# Deck.net
KiCad netlist of a schematic drawn in Altium Designer
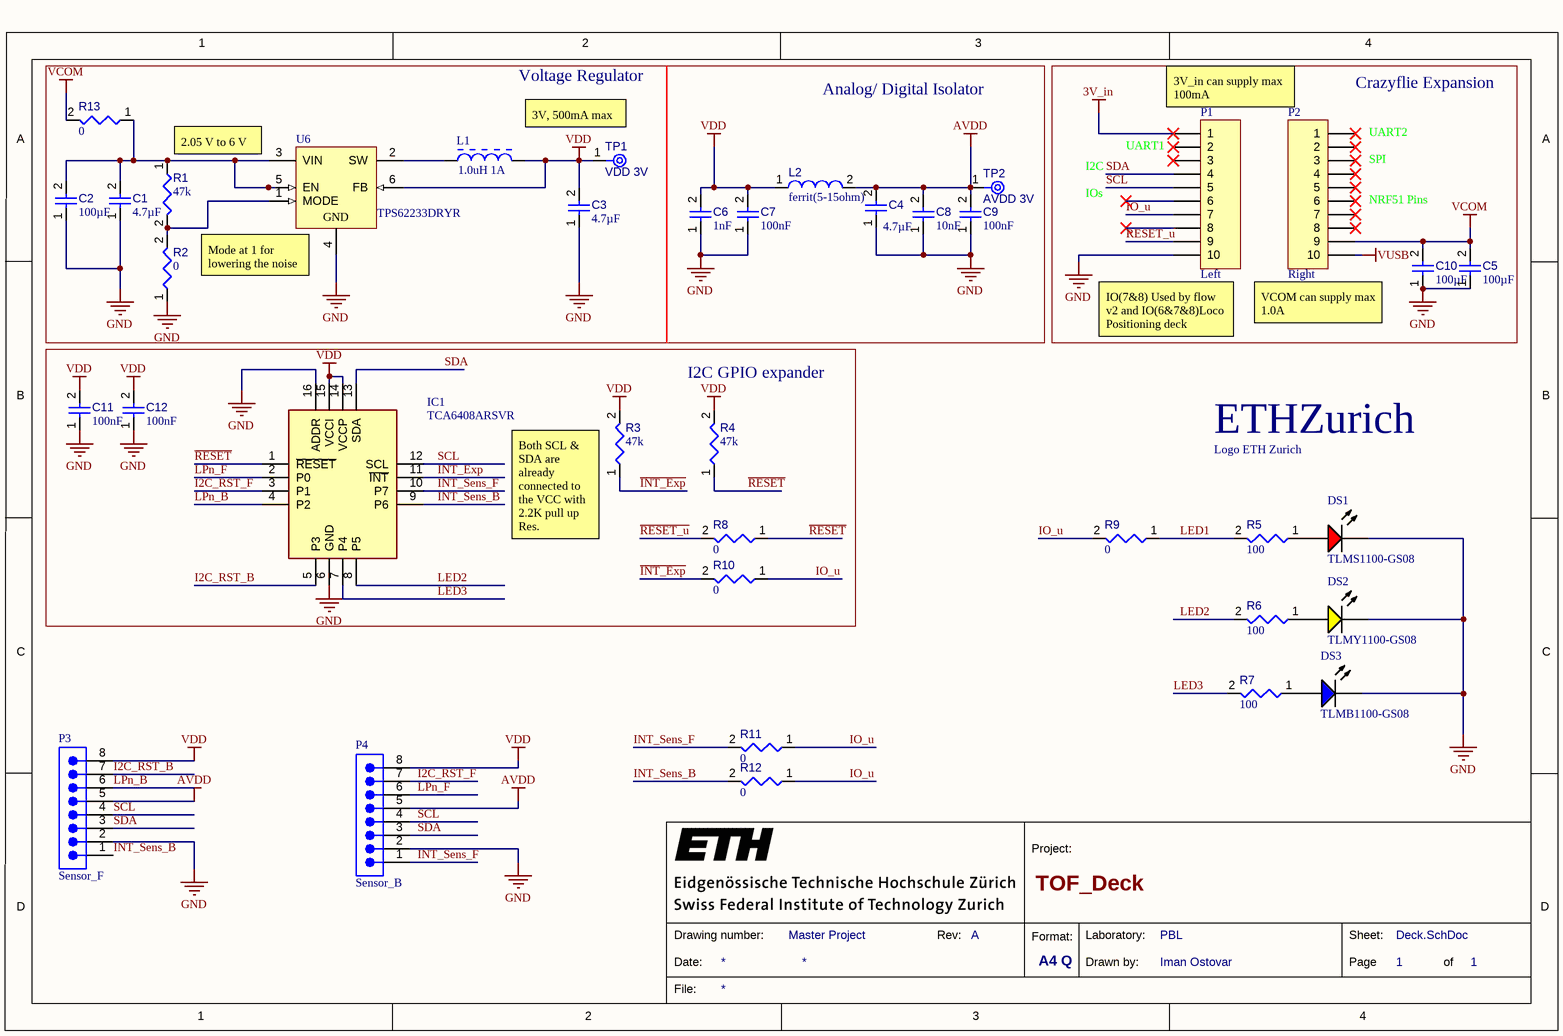
[diagram p0: Deck.SchDoc]

(export (version "E")
  (design (tool "Eeschema 10.0.6"))
  (components
    (comp (ref "A1")
      (value "Logo ETH Zurich")
      (footprint "eth-zurich_3mm")
      (libsource (lib "Sensor_Node_Shield") (part "CMP-00038-1"))
    )
    (comp (ref "C1")
      (value "4.7µF")
      (footprint "CAPC1005X55X25ML5T10")
      (description "Chip Capacitor, 1 uF, +/- 10%, 6.3 V, 1005 (0402 Metric)")
      (fields (field (name "TOLERANCE") "10%") (field (name "Comment") "Capacitor 1 uF +/- 10% 6.3 V 1005"))
      (libsource (lib "ETH Zurich") (part "CAP-NP-2"))
    )
    (comp (ref "C2")
      (value "100µF")
      (footprint "CAPC0805(2012)145_L")
      (description "Chip Capacitor, 100µF +/-20%, 6.3V, 0805, Thickness 1.45 mm")
      (fields (field (name "TOLERANCE") "10%") (field (name "Comment") "Capacitor 100µF +/-20% 6.3V 0805"))
      (libsource (lib "ETH Zurich") (part "CAP-NP-2"))
    )
    (comp (ref "C3")
      (value "4.7µF")
      (footprint "CAPC1005X55X25ML5T10")
      (description "Chip Capacitor, 1 uF, +/- 10%, 6.3 V, 1005 (0402 Metric)")
      (fields (field (name "TOLERANCE") "10%") (field (name "Comment") "Capacitor 1 uF +/- 10% 6.3 V 1005"))
      (libsource (lib "ETH Zurich") (part "CAP-NP-2"))
    )
    (comp (ref "C4")
      (value "4.7µF")
      (footprint "CAPC1005X55X25ML5T10")
      (description "Chip Capacitor, 1 uF, +/- 10%, 6.3 V, 1005 (0402 Metric)")
      (fields (field (name "TOLERANCE") "10%") (field (name "Comment") "Capacitor 1 uF +/- 10% 6.3 V 1005"))
      (libsource (lib "ETH Zurich") (part "CAP-NP-2"))
    )
    (comp (ref "C5")
      (value "100µF")
      (footprint "CAPC0805(2012)145_L")
      (description "Chip Capacitor, 100µF +/-20%, 6.3V, 0805, Thickness 1.45 mm")
      (fields (field (name "TOLERANCE") "10%") (field (name "Comment") "Capacitor 100µF +/-20% 6.3V 0805"))
      (libsource (lib "ETH Zurich") (part "CAP-NP-2"))
    )
    (comp (ref "C6")
      (value "1nF")
      (footprint "CAPC0402(1005)60_L")
      (description "Chip Capacitor, 100nF +/-20%, 25V, 0402, Thickness 0.6 mm")
      (fields (field (name "TOLERANCE") "10%") (field (name "Comment") "Capacitor 100nF +/-20% 25V 0402"))
      (libsource (lib "ETH Zurich") (part "CAP-NP-2"))
    )
    (comp (ref "C7")
      (value "100nF")
      (footprint "CAPC0402(1005)60_L")
      (description "Chip Capacitor, 100nF +/-20%, 25V, 0402, Thickness 0.6 mm")
      (fields (field (name "TOLERANCE") "10%") (field (name "Comment") "Capacitor 100nF +/-20% 25V 0402"))
      (libsource (lib "ETH Zurich") (part "CAP-NP-2"))
    )
    (comp (ref "C8")
      (value "10nF")
      (footprint "CAPC0402(1005)60_L")
      (description "Chip Capacitor, 100nF +/-20%, 25V, 0402, Thickness 0.6 mm")
      (fields (field (name "TOLERANCE") "10%") (field (name "Comment") "Capacitor 100nF +/-20% 25V 0402"))
      (libsource (lib "ETH Zurich") (part "CAP-NP-2"))
    )
    (comp (ref "C9")
      (value "100nF")
      (footprint "CAPC0402(1005)60_L")
      (description "Chip Capacitor, 100nF +/-20%, 25V, 0402, Thickness 0.6 mm")
      (fields (field (name "TOLERANCE") "10%") (field (name "Comment") "Capacitor 100nF +/-20% 25V 0402"))
      (libsource (lib "ETH Zurich") (part "CAP-NP-2"))
    )
    (comp (ref "C10")
      (value "100µF")
      (footprint "CAPC0805(2012)145_L")
      (description "Chip Capacitor, 100µF +/-20%, 6.3V, 0805, Thickness 1.45 mm")
      (fields (field (name "TOLERANCE") "10%") (field (name "Comment") "Capacitor 100µF +/-20% 6.3V 0805"))
      (libsource (lib "ETH Zurich") (part "CAP-NP-2"))
    )
    (comp (ref "C11")
      (value "100nF")
      (footprint "CAPC0402(1005)60_L")
      (description "Chip Capacitor, 100nF +/-20%, 25V, 0402, Thickness 0.6 mm")
      (fields (field (name "TOLERANCE") "10%") (field (name "Comment") "Capacitor 100nF +/-20% 25V 0402"))
      (libsource (lib "ETH Zurich") (part "CAP-NP-2"))
    )
    (comp (ref "C12")
      (value "100nF")
      (footprint "CAPC0402(1005)60_L")
      (description "Chip Capacitor, 100nF +/-20%, 25V, 0402, Thickness 0.6 mm")
      (fields (field (name "TOLERANCE") "10%") (field (name "Comment") "Capacitor 100nF +/-20% 25V 0402"))
      (libsource (lib "ETH Zurich") (part "CAP-NP-2"))
    )
    (comp (ref "DS1")
      (value "TLMS1100-GS08")
      (footprint "VISH-TLMX1100_V")
      (description "Red Led, 20mA, 2.1 V, -40 to 100 degC, 2-Pin SMD (0603), RoHS, Tape and Reel")
      (fields (field (name "MANUFACTURER") "Vishay Semiconductor") (field (name "POWER") "90mW"))
      (libsource (lib "ETH Zurich") (part "LED-RED-AK-2"))
    )
    (comp (ref "DS2")
      (value "TLMY1100-GS08")
      (footprint "VISH-TLMX1100-2_V")
      (description "Yellow LED, 20 mA, 2.1 V, -40 to 100 degC, 2-Pin SMD (0603), RoHS, Tape and Reel")
      (fields (field (name "MANUFACTURER") "Vishay Semiconductor") (field (name "POWER") "90mW"))
      (libsource (lib "ETH Zurich") (part "LED-YELLOW-AK-2"))
    )
    (comp (ref "DS3")
      (value "TLMB1100-GS08")
      (footprint "VISH-TLMX1100-2_V")
      (description "Blue LED, 10 mA, 3.9 V, -40 to 100 degC, 2-Pin SMD (0603), RoHS, Tape and Reel")
      (fields (field (name "POWER") "68mW") (field (name "MANUFACTURER") "Vishay Semiconductor"))
      (libsource (lib "ETH Zurich") (part "LED-BLUE-AK-2"))
    )
    (comp (ref "IC1")
      (value "TCA6408ARSVR")
      (footprint "SamacSys:QFN40P180X260X55-16N")
      (description "Integrated Circuit")
      (fields (field (name "MOUSER PART NUMBER") "595-TCA6408ARSVR"))
      (libsource (lib "*") (part "TCA6408ARSVR"))
    )
    (comp (ref "L1")
      (value "1.0uH 1A")
      (footprint "INDC2013X105X50ML20T20")
      (description "1.0uH 1150mA")
      (fields (field (name "TOLERANCE") "25%") (field (name "MANUFACTURER") "Murata"))
      (libsource (lib "ETH Zurich") (part "IND-FB-2"))
    )
    (comp (ref "L2")
      (value "ferrit(5-15ohm)")
      (footprint "MURA-LQP15MN3N6B02D-2_M")
      (description "Inductor, 500 MHz, 500 mA, 5 Ohm, -40 to 85 degC, 01005 (0402 Metric),")
      (fields (field (name "MANUFACTURER") "Murata") (field (name "Comment") "LQP15MN3N6B02D"))
      (libsource (lib "ETH Zurich") (part "IND-2"))
    )
    (comp (ref "P1")
      (value "Left")
      (footprint "crazyflie-header:PCBComponent_1")
      (description "Header, 10-Pin")
      (fields (field (name "PUBLISHER") "Altium Limited"))
      (libsource (lib "") (part "MHDR1X10_1"))
    )
    (comp (ref "P2")
      (value "Right")
      (footprint "crazyflie-header:PCBComponent_1")
      (description "Header, 10-Pin")
      (fields (field (name "PUBLISHER") "Altium Limited"))
      (libsource (lib "Miscellaneous Connectors") (part "MHDR1X10"))
    )
    (comp (ref "P3")
      (value "Sensor_F")
      (footprint "M50-3930842")
      (description "Connector Header Through Hole, Right Angle 8 position 0.050\" (1.27mm)")
      (libsource (lib "ETHZ Vault") (part "CON-1x8-Male"))
    )
    (comp (ref "P4")
      (value "Sensor_B")
      (footprint "M50-3930842")
      (description "Connector Header Through Hole, Right Angle 8 position 0.050\" (1.27mm)")
      (libsource (lib "ETHZ Vault") (part "CON-1x8-Male"))
    )
    (comp (ref "R1")
      (value "47k")
      (footprint "RESC0402(1005)_L")
      (description "Chip Resistor, 47,5 kOhms, +/-1 %, 63 mW, -55 to 155 degC, 0402")
      (fields (field (name "POWER") "63mW") (field (name "TOLERANCE") "1%"))
      (libsource (lib "ETH Zurich") (part "RES-2"))
    )
    (comp (ref "R2")
      (value "0")
      (footprint "RESC0402(1005)_L")
      (description "Jumper 0402")
      (libsource (lib "ETH Zurich") (part "RES-2"))
    )
    (comp (ref "R3")
      (value "47k")
      (footprint "RESC0402(1005)_L")
      (description "Chip Resistor, 47,5 kOhms, +/-1 %, 63 mW, -55 to 155 degC, 0402")
      (fields (field (name "POWER") "63mW") (field (name "TOLERANCE") "1%"))
      (libsource (lib "ETH Zurich") (part "RES-2"))
    )
    (comp (ref "R4")
      (value "47k")
      (footprint "RESC0402(1005)_L")
      (description "Chip Resistor, 47,5 kOhms, +/-1 %, 63 mW, -55 to 155 degC, 0402")
      (fields (field (name "POWER") "63mW") (field (name "TOLERANCE") "1%"))
      (libsource (lib "ETH Zurich") (part "RES-2"))
    )
    (comp (ref "R5")
      (value "100")
      (footprint "RESC0402(1005)_L")
      (description "Chip Resistor, 47,5 kOhms, +/-1 %, 63 mW, -55 to 155 degC, 0402")
      (fields (field (name "POWER") "63mW") (field (name "TOLERANCE") "1%"))
      (libsource (lib "ETH Zurich") (part "RES-2"))
    )
    (comp (ref "R6")
      (value "100")
      (footprint "RESC0402(1005)_L")
      (description "Chip Resistor, 47,5 kOhms, +/-1 %, 63 mW, -55 to 155 degC, 0402")
      (fields (field (name "POWER") "63mW") (field (name "TOLERANCE") "1%"))
      (libsource (lib "ETH Zurich") (part "RES-2"))
    )
    (comp (ref "R7")
      (value "100")
      (footprint "RESC0402(1005)_L")
      (description "Chip Resistor, 47,5 kOhms, +/-1 %, 63 mW, -55 to 155 degC, 0402")
      (fields (field (name "POWER") "63mW") (field (name "TOLERANCE") "1%"))
      (libsource (lib "ETH Zurich") (part "RES-2"))
    )
    (comp (ref "R8")
      (value "0")
      (footprint "RESC0402(1005)_L")
      (description "Jumper 0402")
      (libsource (lib "ETH Zurich") (part "RES-2"))
    )
    (comp (ref "R9")
      (value "0")
      (footprint "RESC0402(1005)_L")
      (description "Jumper 0402")
      (libsource (lib "ETH Zurich") (part "RES-2"))
    )
    (comp (ref "R10")
      (value "0")
      (footprint "RESC0402(1005)_L")
      (description "Jumper 0402")
      (libsource (lib "ETH Zurich") (part "RES-2"))
    )
    (comp (ref "R11")
      (value "0")
      (footprint "RESC0402(1005)_L")
      (description "Jumper 0402")
      (libsource (lib "ETH Zurich") (part "RES-2"))
    )
    (comp (ref "R12")
      (value "0")
      (footprint "RESC0402(1005)_L")
      (description "Jumper 0402")
      (libsource (lib "ETH Zurich") (part "RES-2"))
    )
    (comp (ref "R13")
      (value "0")
      (footprint "RESC0402(1005)_L")
      (description "Current sensing jumper OR Fuse")
      (fields (field (name "Comment") "Jumper 0402"))
      (libsource (lib "ETH Zurich") (part "RES-2"))
    )
    (comp (ref "TP1")
      (value "VDD 3V")
      (footprint "TP06R")
      (description "0.6mm round")
      (libsource (lib "ETH Zurich") (part "CMP-001-0001-4"))
    )
    (comp (ref "TP2")
      (value "AVDD 3V")
      (footprint "TP06R")
      (description "0.6mm round")
      (libsource (lib "ETH Zurich") (part "CMP-001-0001-4"))
    )
    (comp (ref "U6")
      (value "TPS62233DRYR")
      (footprint "DRY0006A")
      (fields (field (name "MANUFACTURER") "Texas Instruments"))
      (libsource (lib "Altium Content Vault") (part "TI-TPS62233DRY6"))
    )
  )
  (nets
    (net (code "1") (name "/I2C_RST_B") (class "Default")
      (node (ref "IC1") (pin "5") (pinfunction "P3_5") (pintype "passive"))
      (node (ref "P3") (pin "7") (pinfunction "7_7") (pintype "passive"))
    )
    (net (code "2") (name "/I2C_RST_F") (class "Default")
      (node (ref "IC1") (pin "3") (pinfunction "P1_3") (pintype "passive"))
      (node (ref "P4") (pin "7") (pinfunction "7_7") (pintype "passive"))
    )
    (net (code "3") (name "/INT_Exp") (class "Default")
      (node (ref "IC1") (pin "11") (pinfunction "~{INT}_11") (pintype "passive"))
      (node (ref "R10") (pin "2") (pinfunction "2_2") (pintype "passive"))
      (node (ref "R3") (pin "1") (pinfunction "1_1") (pintype "passive"))
    )
    (net (code "4") (name "/INT_Sens_B") (class "Default")
      (node (ref "IC1") (pin "9") (pinfunction "P6_9") (pintype "passive"))
      (node (ref "P3") (pin "1") (pinfunction "1_1") (pintype "passive"))
      (node (ref "R12") (pin "2") (pinfunction "2_2") (pintype "passive"))
    )
    (net (code "5") (name "/INT_Sens_F") (class "Default")
      (node (ref "IC1") (pin "10") (pinfunction "P7_10") (pintype "passive"))
      (node (ref "P4") (pin "1") (pinfunction "1_1") (pintype "passive"))
      (node (ref "R11") (pin "2") (pinfunction "2_2") (pintype "passive"))
    )
    (net (code "6") (name "/IO_u") (class "Default")
      (node (ref "P1") (pin "7") (pinfunction "7_7") (pintype "passive"))
      (node (ref "R10") (pin "1") (pinfunction "1_1") (pintype "passive"))
      (node (ref "R11") (pin "1") (pinfunction "1_1") (pintype "passive"))
      (node (ref "R12") (pin "1") (pinfunction "1_1") (pintype "passive"))
      (node (ref "R9") (pin "2") (pinfunction "2_2") (pintype "passive"))
    )
    (net (code "7") (name "/LED1") (class "Default")
      (node (ref "R5") (pin "2") (pinfunction "2_2") (pintype "passive"))
      (node (ref "R9") (pin "1") (pinfunction "1_1") (pintype "passive"))
    )
    (net (code "8") (name "/LED2") (class "Default")
      (node (ref "IC1") (pin "8") (pinfunction "P5_8") (pintype "passive"))
      (node (ref "R6") (pin "2") (pinfunction "2_2") (pintype "passive"))
    )
    (net (code "9") (name "/LED3") (class "Default")
      (node (ref "IC1") (pin "7") (pinfunction "P4_7") (pintype "passive"))
      (node (ref "R7") (pin "2") (pinfunction "2_2") (pintype "passive"))
    )
    (net (code "10") (name "/LPn_B") (class "Default")
      (node (ref "IC1") (pin "4") (pinfunction "P2_4") (pintype "passive"))
      (node (ref "P3") (pin "6") (pinfunction "6_6") (pintype "passive"))
    )
    (net (code "11") (name "/LPn_F") (class "Default")
      (node (ref "IC1") (pin "2") (pinfunction "P0_2") (pintype "passive"))
      (node (ref "P4") (pin "6") (pinfunction "6_6") (pintype "passive"))
    )
    (net (code "12") (name "/RESET") (class "Default")
      (node (ref "IC1") (pin "1") (pinfunction "~{RESET}_1") (pintype "passive"))
      (node (ref "R4") (pin "1") (pinfunction "1_1") (pintype "passive"))
      (node (ref "R8") (pin "1") (pinfunction "1_1") (pintype "passive"))
    )
    (net (code "13") (name "/RESET_u") (class "Default")
      (node (ref "P1") (pin "9") (pinfunction "9_9") (pintype "passive"))
      (node (ref "R8") (pin "2") (pinfunction "2_2") (pintype "passive"))
    )
    (net (code "14") (name "/SCL") (class "Default")
      (node (ref "IC1") (pin "12") (pinfunction "SCL_12") (pintype "passive"))
      (node (ref "P1") (pin "5") (pinfunction "5_5") (pintype "passive"))
      (node (ref "P3") (pin "4") (pinfunction "4_4") (pintype "passive"))
      (node (ref "P4") (pin "4") (pinfunction "4_4") (pintype "passive"))
    )
    (net (code "15") (name "/SDA") (class "Default")
      (node (ref "IC1") (pin "13") (pinfunction "SDA_13") (pintype "passive"))
      (node (ref "P1") (pin "4") (pinfunction "4_4") (pintype "passive"))
      (node (ref "P3") (pin "3") (pinfunction "3_3") (pintype "passive"))
      (node (ref "P4") (pin "3") (pinfunction "3_3") (pintype "passive"))
    )
    (net (code "16") (name "3V_in") (class "Default")
      (node (ref "P1") (pin "1") (pinfunction "1_1") (pintype "passive"))
    )
    (net (code "17") (name "AVDD") (class "Default")
      (node (ref "C4") (pin "2") (pinfunction "2_2") (pintype "passive"))
      (node (ref "C8") (pin "2") (pinfunction "2_2") (pintype "passive"))
      (node (ref "C9") (pin "2") (pinfunction "2_2") (pintype "passive"))
      (node (ref "L2") (pin "2") (pinfunction "2_2") (pintype "passive"))
      (node (ref "P3") (pin "5") (pinfunction "5_5") (pintype "passive"))
      (node (ref "P4") (pin "5") (pinfunction "5_5") (pintype "passive"))
      (node (ref "TP2") (pin "1") (pinfunction "TP_1") (pintype "passive"))
    )
    (net (code "18") (name "GND") (class "Default")
      (node (ref "C1") (pin "1") (pinfunction "1_1") (pintype "passive"))
      (node (ref "C10") (pin "1") (pinfunction "1_1") (pintype "passive"))
      (node (ref "C11") (pin "1") (pinfunction "1_1") (pintype "passive"))
      (node (ref "C12") (pin "1") (pinfunction "1_1") (pintype "passive"))
      (node (ref "C2") (pin "1") (pinfunction "1_1") (pintype "passive"))
      (node (ref "C3") (pin "1") (pinfunction "1_1") (pintype "passive"))
      (node (ref "C4") (pin "1") (pinfunction "1_1") (pintype "passive"))
      (node (ref "C5") (pin "1") (pinfunction "1_1") (pintype "passive"))
      (node (ref "C6") (pin "1") (pinfunction "1_1") (pintype "passive"))
      (node (ref "C7") (pin "1") (pinfunction "1_1") (pintype "passive"))
      (node (ref "C8") (pin "1") (pinfunction "1_1") (pintype "passive"))
      (node (ref "C9") (pin "1") (pinfunction "1_1") (pintype "passive"))
      (node (ref "DS1") (pin "2") (pinfunction "K_2") (pintype "passive"))
      (node (ref "DS2") (pin "2") (pinfunction "K_2") (pintype "passive"))
      (node (ref "DS3") (pin "2") (pinfunction "K_2") (pintype "passive"))
      (node (ref "IC1") (pin "16") (pinfunction "ADDR_16") (pintype "passive"))
      (node (ref "IC1") (pin "6") (pinfunction "GND_6") (pintype "passive"))
      (node (ref "P1") (pin "10") (pinfunction "10_10") (pintype "passive"))
      (node (ref "P3") (pin "2") (pinfunction "2_2") (pintype "passive"))
      (node (ref "P4") (pin "2") (pinfunction "2_2") (pintype "passive"))
      (node (ref "R2") (pin "1") (pinfunction "1_1") (pintype "passive"))
      (node (ref "U6") (pin "4") (pinfunction "GND_4") (pintype "power_in"))
    )
    (net (code "19") (name "Net-(DS1-A)") (class "Default")
      (node (ref "DS1") (pin "1") (pinfunction "A_1") (pintype "passive"))
      (node (ref "R5") (pin "1") (pinfunction "1_1") (pintype "passive"))
    )
    (net (code "20") (name "Net-(DS2-A)") (class "Default")
      (node (ref "DS2") (pin "1") (pinfunction "A_1") (pintype "passive"))
      (node (ref "R6") (pin "1") (pinfunction "1_1") (pintype "passive"))
    )
    (net (code "21") (name "Net-(DS3-A)") (class "Default")
      (node (ref "DS3") (pin "1") (pinfunction "A_1") (pintype "passive"))
      (node (ref "R7") (pin "1") (pinfunction "1_1") (pintype "passive"))
    )
    (net (code "22") (name "Net-(U6-EN)") (class "Default")
      (node (ref "C1") (pin "2") (pinfunction "2_2") (pintype "passive"))
      (node (ref "C2") (pin "2") (pinfunction "2_2") (pintype "passive"))
      (node (ref "R1") (pin "1") (pinfunction "1_1") (pintype "passive"))
      (node (ref "R13") (pin "1") (pinfunction "1_1") (pintype "passive"))
      (node (ref "U6") (pin "3") (pinfunction "VIN_3") (pintype "power_in"))
      (node (ref "U6") (pin "5") (pinfunction "EN_5") (pintype "input"))
    )
    (net (code "23") (name "Net-(U6-MODE)") (class "Default")
      (node (ref "R1") (pin "2") (pinfunction "2_2") (pintype "passive"))
      (node (ref "R2") (pin "2") (pinfunction "2_2") (pintype "passive"))
      (node (ref "U6") (pin "1") (pinfunction "MODE_1") (pintype "input"))
    )
    (net (code "24") (name "Net-(U6-SW)") (class "Default")
      (node (ref "L1") (pin "1") (pinfunction "1_1") (pintype "passive"))
      (node (ref "U6") (pin "2") (pinfunction "SW_2") (pintype "power_in"))
    )
    (net (code "25") (name "VCOM") (class "Default")
      (node (ref "C10") (pin "2") (pinfunction "2_2") (pintype "passive"))
      (node (ref "C5") (pin "2") (pinfunction "2_2") (pintype "passive"))
      (node (ref "P2") (pin "9") (pinfunction "9_9") (pintype "passive"))
      (node (ref "R13") (pin "2") (pinfunction "2_2") (pintype "passive"))
    )
    (net (code "26") (name "VDD") (class "Default")
      (node (ref "C11") (pin "2") (pinfunction "2_2") (pintype "passive"))
      (node (ref "C12") (pin "2") (pinfunction "2_2") (pintype "passive"))
      (node (ref "C3") (pin "2") (pinfunction "2_2") (pintype "passive"))
      (node (ref "C6") (pin "2") (pinfunction "2_2") (pintype "passive"))
      (node (ref "C7") (pin "2") (pinfunction "2_2") (pintype "passive"))
      (node (ref "IC1") (pin "14") (pinfunction "VCCP_14") (pintype "passive"))
      (node (ref "IC1") (pin "15") (pinfunction "VCCI_15") (pintype "passive"))
      (node (ref "L1") (pin "2") (pinfunction "2_2") (pintype "passive"))
      (node (ref "L2") (pin "1") (pinfunction "1_1") (pintype "passive"))
      (node (ref "P3") (pin "8") (pinfunction "8_8") (pintype "passive"))
      (node (ref "P4") (pin "8") (pinfunction "8_8") (pintype "passive"))
      (node (ref "R3") (pin "2") (pinfunction "2_2") (pintype "passive"))
      (node (ref "R4") (pin "2") (pinfunction "2_2") (pintype "passive"))
      (node (ref "TP1") (pin "1") (pinfunction "TP_1") (pintype "passive"))
      (node (ref "U6") (pin "6") (pinfunction "FB_6") (pintype "input"))
    )
    (net (code "27") (name "VUSB") (class "Default")
      (node (ref "P2") (pin "10") (pinfunction "10_10") (pintype "passive"))
    )
    (net (code "28") (name "unconnected-(P1-Pad2)") (class "Default")
      (node (ref "P1") (pin "2") (pinfunction "2_2") (pintype "passive+no_connect"))
    )
    (net (code "29") (name "unconnected-(P1-Pad3)") (class "Default")
      (node (ref "P1") (pin "3") (pinfunction "3_3") (pintype "passive+no_connect"))
    )
    (net (code "30") (name "unconnected-(P1-Pad6)") (class "Default")
      (node (ref "P1") (pin "6") (pinfunction "6_6") (pintype "passive+no_connect"))
    )
    (net (code "31") (name "unconnected-(P1-Pad8)") (class "Default")
      (node (ref "P1") (pin "8") (pinfunction "8_8") (pintype "passive+no_connect"))
    )
    (net (code "32") (name "unconnected-(P2-Pad1)") (class "Default")
      (node (ref "P2") (pin "1") (pinfunction "1_1") (pintype "passive+no_connect"))
    )
    (net (code "33") (name "unconnected-(P2-Pad2)") (class "Default")
      (node (ref "P2") (pin "2") (pinfunction "2_2") (pintype "passive+no_connect"))
    )
    (net (code "34") (name "unconnected-(P2-Pad3)") (class "Default")
      (node (ref "P2") (pin "3") (pinfunction "3_3") (pintype "passive+no_connect"))
    )
    (net (code "35") (name "unconnected-(P2-Pad4)") (class "Default")
      (node (ref "P2") (pin "4") (pinfunction "4_4") (pintype "passive+no_connect"))
    )
    (net (code "36") (name "unconnected-(P2-Pad5)") (class "Default")
      (node (ref "P2") (pin "5") (pinfunction "5_5") (pintype "passive+no_connect"))
    )
    (net (code "37") (name "unconnected-(P2-Pad6)") (class "Default")
      (node (ref "P2") (pin "6") (pinfunction "6_6") (pintype "passive+no_connect"))
    )
    (net (code "38") (name "unconnected-(P2-Pad7)") (class "Default")
      (node (ref "P2") (pin "7") (pinfunction "7_7") (pintype "passive+no_connect"))
    )
    (net (code "39") (name "unconnected-(P2-Pad8)") (class "Default")
      (node (ref "P2") (pin "8") (pinfunction "8_8") (pintype "passive+no_connect"))
    )
  )
)
